# track-hold-lvc-sampler.net
KiCad netlist of a schematic drawn in EAGLE
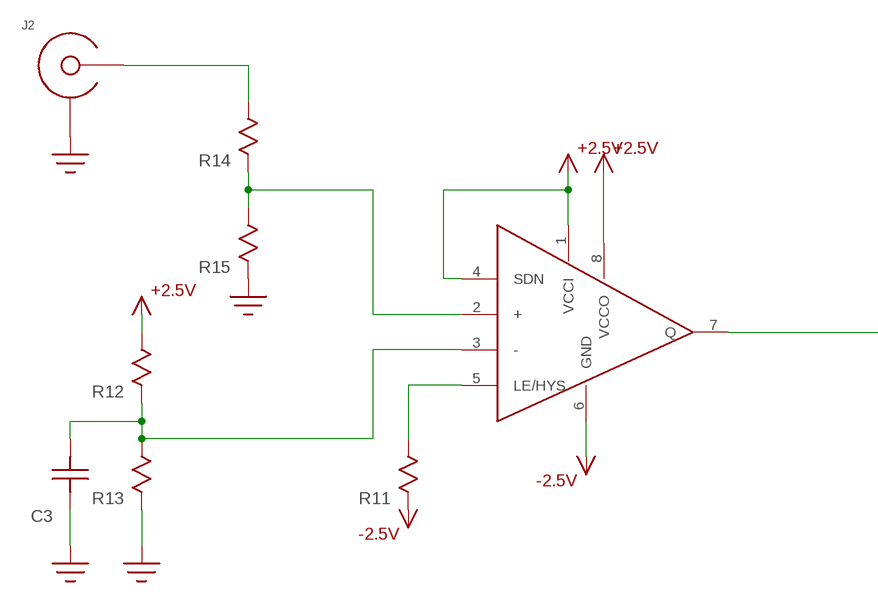
[diagram p0: schematic, sheet 1, part 1 of 2]
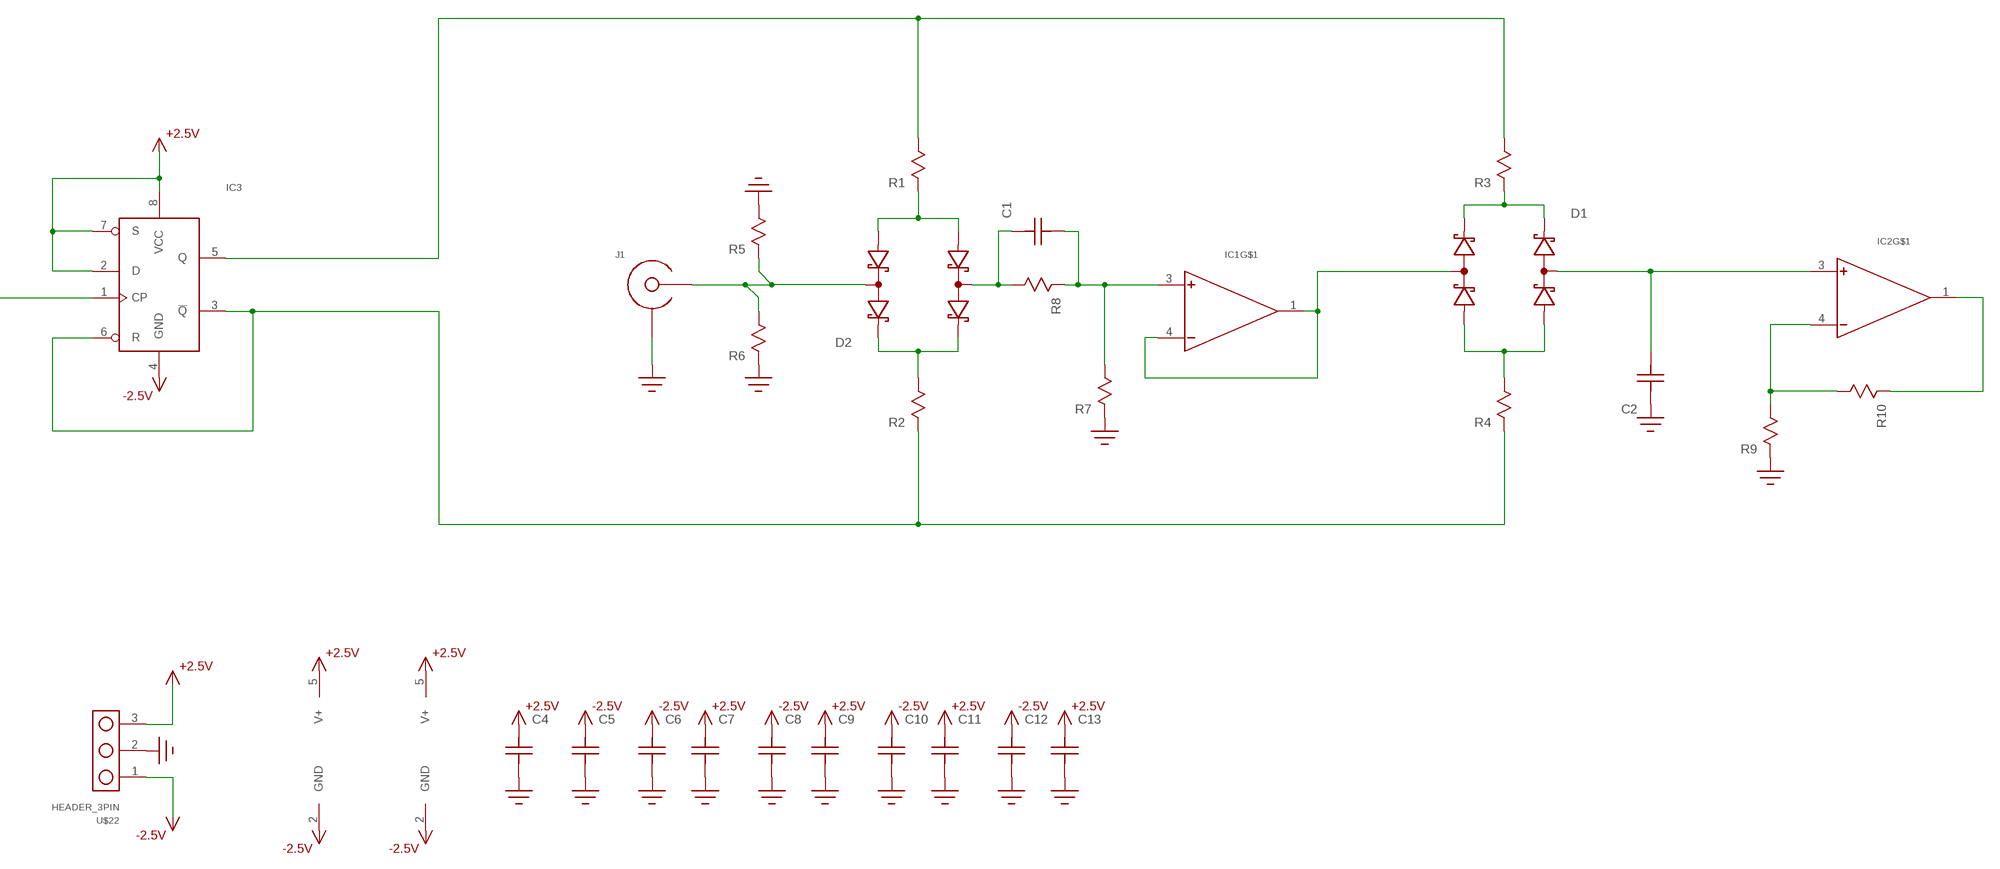
[diagram p1: schematic, sheet 1, part 2 of 2]

(export (version "E")
  (design (tool "Eeschema 10.0.6"))
  (components
    (comp (ref "C1")
      (value "C0603")
      (footprint "eagle-import:C0603")
      (libsource (lib "eagle-import") (part "C0603"))
    )
    (comp (ref "C2")
      (value "C0603")
      (footprint "eagle-import:C0603")
      (libsource (lib "eagle-import") (part "C0603"))
    )
    (comp (ref "C3")
      (value "C0603")
      (footprint "eagle-import:C0603")
      (libsource (lib "eagle-import") (part "C0603"))
    )
    (comp (ref "C4")
      (value "C1206")
      (footprint "eagle-import:1206")
      (libsource (lib "eagle-import") (part "C1206"))
    )
    (comp (ref "C5")
      (value "C1206")
      (footprint "eagle-import:1206")
      (libsource (lib "eagle-import") (part "C1206"))
    )
    (comp (ref "C6")
      (value "C0603")
      (footprint "eagle-import:C0603")
      (libsource (lib "eagle-import") (part "C0603"))
    )
    (comp (ref "C7")
      (value "C0603")
      (footprint "eagle-import:C0603")
      (libsource (lib "eagle-import") (part "C0603"))
    )
    (comp (ref "C8")
      (value "C0603")
      (footprint "eagle-import:C0603")
      (libsource (lib "eagle-import") (part "C0603"))
    )
    (comp (ref "C9")
      (value "C0603")
      (footprint "eagle-import:C0603")
      (libsource (lib "eagle-import") (part "C0603"))
    )
    (comp (ref "C10")
      (value "C0603")
      (footprint "eagle-import:C0603")
      (libsource (lib "eagle-import") (part "C0603"))
    )
    (comp (ref "C11")
      (value "C0603")
      (footprint "eagle-import:C0603")
      (libsource (lib "eagle-import") (part "C0603"))
    )
    (comp (ref "C12")
      (value "C0603")
      (footprint "eagle-import:C0603")
      (libsource (lib "eagle-import") (part "C0603"))
    )
    (comp (ref "C13")
      (value "C0603")
      (footprint "eagle-import:C0603")
      (libsource (lib "eagle-import") (part "C0603"))
    )
    (comp (ref "D1")
      (value "SMS3923-081")
      (footprint "eagle-import:SC-88")
      (libsource (lib "eagle-import") (part "SMS3923-081"))
    )
    (comp (ref "D2")
      (value "SMS3923-081")
      (footprint "eagle-import:SC-88")
      (libsource (lib "eagle-import") (part "SMS3923-081"))
    )
    (comp (ref "IC1")
      (value "ADA4000TSOT")
      (footprint "eagle-import:TSOT-23")
      (libsource (lib "eagle-import") (part "ADA4000TSOT"))
    )
    (comp (ref "IC2")
      (value "ADA4000TSOT")
      (footprint "eagle-import:TSOT-23")
      (libsource (lib "eagle-import") (part "ADA4000TSOT"))
    )
    (comp (ref "IC3")
      (value "74LVC2G74")
      (footprint "eagle-import:SSOP8")
      (libsource (lib "eagle-import") (part "74LVC2G74"))
    )
    (comp (ref "IC4")
      (value "ADCMP602")
      (footprint "eagle-import:MSOP8")
      (libsource (lib "eagle-import") (part "ADCMP602"))
    )
    (comp (ref "J1")
      (value "SMA-EDGE-LAUNCH4L-4020-TAPER-FIXED")
      (footprint "eagle-import:SMA_EDGE_LAUNCH_4L_4020_TAPER_FIXED")
      (libsource (lib "eagle-import") (part "SMA-EDGE-LAUNCH4L-4020-TAPER-FIXED"))
    )
    (comp (ref "J2")
      (value "SMA-EDGE-LAUNCH4L-4020-TAPER-FIXED")
      (footprint "eagle-import:SMA_EDGE_LAUNCH_4L_4020_TAPER_FIXED")
      (libsource (lib "eagle-import") (part "SMA-EDGE-LAUNCH4L-4020-TAPER-FIXED"))
    )
    (comp (ref "R1")
      (value "R0603")
      (footprint "eagle-import:R0603")
      (libsource (lib "eagle-import") (part "R0603"))
    )
    (comp (ref "R2")
      (value "R0603")
      (footprint "eagle-import:R0603")
      (libsource (lib "eagle-import") (part "R0603"))
    )
    (comp (ref "R3")
      (value "R0603")
      (footprint "eagle-import:R0603")
      (libsource (lib "eagle-import") (part "R0603"))
    )
    (comp (ref "R4")
      (value "R0603")
      (footprint "eagle-import:R0603")
      (libsource (lib "eagle-import") (part "R0603"))
    )
    (comp (ref "R5")
      (value "R0402")
      (footprint "eagle-import:0402")
      (libsource (lib "eagle-import") (part "R0402"))
    )
    (comp (ref "R6")
      (value "R0402")
      (footprint "eagle-import:0402")
      (libsource (lib "eagle-import") (part "R0402"))
    )
    (comp (ref "R7")
      (value "R0603")
      (footprint "eagle-import:R0603")
      (libsource (lib "eagle-import") (part "R0603"))
    )
    (comp (ref "R8")
      (value "R0603")
      (footprint "eagle-import:R0603")
      (libsource (lib "eagle-import") (part "R0603"))
    )
    (comp (ref "R9")
      (value "R0603")
      (footprint "eagle-import:R0603")
      (libsource (lib "eagle-import") (part "R0603"))
    )
    (comp (ref "R10")
      (value "R0603")
      (footprint "eagle-import:R0603")
      (libsource (lib "eagle-import") (part "R0603"))
    )
    (comp (ref "R11")
      (value "R0603")
      (footprint "eagle-import:R0603")
      (libsource (lib "eagle-import") (part "R0603"))
    )
    (comp (ref "R12")
      (value "R0603")
      (footprint "eagle-import:R0603")
      (libsource (lib "eagle-import") (part "R0603"))
    )
    (comp (ref "R13")
      (value "R0603")
      (footprint "eagle-import:R0603")
      (libsource (lib "eagle-import") (part "R0603"))
    )
    (comp (ref "R14")
      (value "R0603")
      (footprint "eagle-import:R0603")
      (libsource (lib "eagle-import") (part "R0603"))
    )
    (comp (ref "R15")
      (value "R0603")
      (footprint "eagle-import:R0603")
      (libsource (lib "eagle-import") (part "R0603"))
    )
    (comp (ref "U$22")
      (value "HEADER_3PIN")
      (footprint "eagle-import:HEADER_3PIN")
      (libsource (lib "eagle-import") (part "HEADER_3PIN"))
    )
  )
  (nets
    (net (code "1") (name "+2.5V") (class "Default")
      (node (ref "C11") (pin "P$2") (pinfunction "P$2_P$2") (pintype "bidirectional"))
      (node (ref "C13") (pin "P$2") (pinfunction "P$2_P$2") (pintype "bidirectional"))
      (node (ref "C4") (pin "P$2") (pinfunction "P$2_P$2") (pintype "bidirectional"))
      (node (ref "C7") (pin "P$2") (pinfunction "P$2_P$2") (pintype "bidirectional"))
      (node (ref "C9") (pin "P$2") (pinfunction "P$2_P$2") (pintype "bidirectional"))
      (node (ref "IC1") (pin "5") (pinfunction "V+_5") (pintype "bidirectional"))
      (node (ref "IC2") (pin "5") (pinfunction "V+_5") (pintype "bidirectional"))
      (node (ref "IC3") (pin "2") (pinfunction "D_2") (pintype "bidirectional"))
      (node (ref "IC3") (pin "7") (pinfunction "S_7") (pintype "bidirectional"))
      (node (ref "IC3") (pin "8") (pinfunction "VCC_8") (pintype "bidirectional"))
      (node (ref "IC4") (pin "1") (pinfunction "VCCI_1") (pintype "bidirectional"))
      (node (ref "IC4") (pin "4") (pinfunction "SDN_4") (pintype "bidirectional"))
      (node (ref "IC4") (pin "8") (pinfunction "VCCO_8") (pintype "bidirectional"))
      (node (ref "R12") (pin "P$2") (pinfunction "P$4_P$2") (pintype "bidirectional"))
      (node (ref "U$22") (pin "3") (pinfunction "3_3") (pintype "bidirectional"))
    )
    (net (code "2") (name "-2.5V") (class "Default")
      (node (ref "C10") (pin "P$2") (pinfunction "P$2_P$2") (pintype "bidirectional"))
      (node (ref "C12") (pin "P$2") (pinfunction "P$2_P$2") (pintype "bidirectional"))
      (node (ref "C5") (pin "P$2") (pinfunction "P$2_P$2") (pintype "bidirectional"))
      (node (ref "C6") (pin "P$2") (pinfunction "P$2_P$2") (pintype "bidirectional"))
      (node (ref "C8") (pin "P$2") (pinfunction "P$2_P$2") (pintype "bidirectional"))
      (node (ref "IC1") (pin "2") (pinfunction "GND_2") (pintype "bidirectional"))
      (node (ref "IC2") (pin "2") (pinfunction "GND_2") (pintype "bidirectional"))
      (node (ref "IC3") (pin "4") (pinfunction "GND_4") (pintype "bidirectional"))
      (node (ref "IC4") (pin "6") (pinfunction "GND_6") (pintype "bidirectional"))
      (node (ref "R11") (pin "P$1") (pinfunction "P$3_P$1") (pintype "bidirectional"))
      (node (ref "U$22") (pin "1") (pinfunction "1_1") (pintype "bidirectional"))
    )
    (net (code "3") (name "GND") (class "Default")
      (node (ref "C10") (pin "P$1") (pinfunction "P$1_P$1") (pintype "bidirectional"))
      (node (ref "C11") (pin "P$1") (pinfunction "P$1_P$1") (pintype "bidirectional"))
      (node (ref "C12") (pin "P$1") (pinfunction "P$1_P$1") (pintype "bidirectional"))
      (node (ref "C13") (pin "P$1") (pinfunction "P$1_P$1") (pintype "bidirectional"))
      (node (ref "C2") (pin "P$2") (pinfunction "P$2_P$2") (pintype "bidirectional"))
      (node (ref "C3") (pin "P$2") (pinfunction "P$2_P$2") (pintype "bidirectional"))
      (node (ref "C4") (pin "P$1") (pinfunction "P$1_P$1") (pintype "bidirectional"))
      (node (ref "C5") (pin "P$1") (pinfunction "P$1_P$1") (pintype "bidirectional"))
      (node (ref "C6") (pin "P$1") (pinfunction "P$1_P$1") (pintype "bidirectional"))
      (node (ref "C7") (pin "P$1") (pinfunction "P$1_P$1") (pintype "bidirectional"))
      (node (ref "C8") (pin "P$1") (pinfunction "P$1_P$1") (pintype "bidirectional"))
      (node (ref "C9") (pin "P$1") (pinfunction "P$1_P$1") (pintype "bidirectional"))
      (node (ref "J1") (pin "BOTTOM_GND") (pinfunction "SHIELD_BOTTOM_GND") (pintype "bidirectional"))
      (node (ref "J1") (pin "GND@1") (pinfunction "SHIELD_GND@1") (pintype "bidirectional"))
      (node (ref "J1") (pin "GND@14") (pinfunction "SHIELD_GND@14") (pintype "bidirectional"))
      (node (ref "J1") (pin "GND@15") (pinfunction "SHIELD_GND@15") (pintype "bidirectional"))
      (node (ref "J1") (pin "GND@16") (pinfunction "SHIELD_GND@16") (pintype "bidirectional"))
      (node (ref "J1") (pin "GND@17") (pinfunction "SHIELD_GND@17") (pintype "bidirectional"))
      (node (ref "J1") (pin "GND@2") (pinfunction "SHIELD_GND@2") (pintype "bidirectional"))
      (node (ref "J1") (pin "GND@3") (pinfunction "SHIELD_GND@3") (pintype "bidirectional"))
      (node (ref "J1") (pin "GND@4") (pinfunction "SHIELD_GND@4") (pintype "bidirectional"))
      (node (ref "J1") (pin "GND@5") (pinfunction "SHIELD_GND@5") (pintype "bidirectional"))
      (node (ref "J1") (pin "GND@6") (pinfunction "SHIELD_GND@6") (pintype "bidirectional"))
      (node (ref "J1") (pin "GND@7") (pinfunction "SHIELD_GND@7") (pintype "bidirectional"))
      (node (ref "J1") (pin "GND@8") (pinfunction "SHIELD_GND@8") (pintype "bidirectional"))
      (node (ref "J1") (pin "GND_PAD1") (pinfunction "SHIELD_GND_PAD1") (pintype "bidirectional"))
      (node (ref "J1") (pin "GND_PAD2") (pinfunction "SHIELD_GND_PAD2") (pintype "bidirectional"))
      (node (ref "J1") (pin "P$1") (pinfunction "SHIELD_P$1") (pintype "bidirectional"))
      (node (ref "J1") (pin "P$2") (pinfunction "SHIELD_P$2") (pintype "bidirectional"))
      (node (ref "J2") (pin "BOTTOM_GND") (pinfunction "SHIELD_BOTTOM_GND") (pintype "bidirectional"))
      (node (ref "J2") (pin "GND@1") (pinfunction "SHIELD_GND@1") (pintype "bidirectional"))
      (node (ref "J2") (pin "GND@14") (pinfunction "SHIELD_GND@14") (pintype "bidirectional"))
      (node (ref "J2") (pin "GND@15") (pinfunction "SHIELD_GND@15") (pintype "bidirectional"))
      (node (ref "J2") (pin "GND@16") (pinfunction "SHIELD_GND@16") (pintype "bidirectional"))
      (node (ref "J2") (pin "GND@17") (pinfunction "SHIELD_GND@17") (pintype "bidirectional"))
      (node (ref "J2") (pin "GND@2") (pinfunction "SHIELD_GND@2") (pintype "bidirectional"))
      (node (ref "J2") (pin "GND@3") (pinfunction "SHIELD_GND@3") (pintype "bidirectional"))
      (node (ref "J2") (pin "GND@4") (pinfunction "SHIELD_GND@4") (pintype "bidirectional"))
      (node (ref "J2") (pin "GND@5") (pinfunction "SHIELD_GND@5") (pintype "bidirectional"))
      (node (ref "J2") (pin "GND@6") (pinfunction "SHIELD_GND@6") (pintype "bidirectional"))
      (node (ref "J2") (pin "GND@7") (pinfunction "SHIELD_GND@7") (pintype "bidirectional"))
      (node (ref "J2") (pin "GND@8") (pinfunction "SHIELD_GND@8") (pintype "bidirectional"))
      (node (ref "J2") (pin "GND_PAD1") (pinfunction "SHIELD_GND_PAD1") (pintype "bidirectional"))
      (node (ref "J2") (pin "GND_PAD2") (pinfunction "SHIELD_GND_PAD2") (pintype "bidirectional"))
      (node (ref "J2") (pin "P$1") (pinfunction "SHIELD_P$1") (pintype "bidirectional"))
      (node (ref "J2") (pin "P$2") (pinfunction "SHIELD_P$2") (pintype "bidirectional"))
      (node (ref "R13") (pin "P$1") (pinfunction "P$3_P$1") (pintype "bidirectional"))
      (node (ref "R15") (pin "P$1") (pinfunction "P$3_P$1") (pintype "bidirectional"))
      (node (ref "R5") (pin "2") (pinfunction "P$4_2") (pintype "bidirectional"))
      (node (ref "R6") (pin "1") (pinfunction "P$3_1") (pintype "bidirectional"))
      (node (ref "R7") (pin "P$1") (pinfunction "P$3_P$1") (pintype "bidirectional"))
      (node (ref "R9") (pin "P$1") (pinfunction "P$3_P$1") (pintype "bidirectional"))
      (node (ref "U$22") (pin "2") (pinfunction "2_2") (pintype "bidirectional"))
    )
    (net (code "4") (name "Net-(D1-ANODE0)") (class "Default")
      (node (ref "D1") (pin "1") (pinfunction "ANODE0_1") (pintype "bidirectional"))
      (node (ref "D1") (pin "6") (pinfunction "ANODE1_6") (pintype "bidirectional"))
      (node (ref "R4") (pin "P$2") (pinfunction "P$4_P$2") (pintype "bidirectional"))
    )
    (net (code "5") (name "Net-(D1-CATHODE0)") (class "Default")
      (node (ref "D1") (pin "3") (pinfunction "CATHODE0_3") (pintype "bidirectional"))
      (node (ref "D1") (pin "4") (pinfunction "CATHODE1_4") (pintype "bidirectional"))
      (node (ref "R3") (pin "P$1") (pinfunction "P$3_P$1") (pintype "bidirectional"))
    )
    (net (code "6") (name "Net-(D1-COMMON0)") (class "Default")
      (node (ref "C2") (pin "P$1") (pinfunction "P$1_P$1") (pintype "bidirectional"))
      (node (ref "D1") (pin "2") (pinfunction "COMMON0_2") (pintype "bidirectional"))
      (node (ref "IC2") (pin "3") (pinfunction "+_3") (pintype "bidirectional"))
    )
    (net (code "7") (name "Net-(D1-COMMON1)") (class "Default")
      (node (ref "D1") (pin "5") (pinfunction "COMMON1_5") (pintype "bidirectional"))
      (node (ref "IC1") (pin "1") (pinfunction "OUT_1") (pintype "bidirectional"))
      (node (ref "IC1") (pin "4") (pinfunction "-_4") (pintype "bidirectional"))
    )
    (net (code "8") (name "Net-(D2-ANODE0)") (class "Default")
      (node (ref "D2") (pin "1") (pinfunction "ANODE0_1") (pintype "bidirectional"))
      (node (ref "D2") (pin "6") (pinfunction "ANODE1_6") (pintype "bidirectional"))
      (node (ref "R1") (pin "P$1") (pinfunction "P$3_P$1") (pintype "bidirectional"))
    )
    (net (code "9") (name "Net-(D2-CATHODE0)") (class "Default")
      (node (ref "D2") (pin "3") (pinfunction "CATHODE0_3") (pintype "bidirectional"))
      (node (ref "D2") (pin "4") (pinfunction "CATHODE1_4") (pintype "bidirectional"))
      (node (ref "R2") (pin "P$2") (pinfunction "P$4_P$2") (pintype "bidirectional"))
    )
    (net (code "10") (name "Net-(D2-COMMON0)") (class "Default")
      (node (ref "D2") (pin "2") (pinfunction "COMMON0_2") (pintype "bidirectional"))
      (node (ref "J1") (pin "CENTER@1") (pinfunction "CENTER_CENTER@1") (pintype "bidirectional"))
      (node (ref "J1") (pin "P$3") (pinfunction "CENTER_P$3") (pintype "bidirectional"))
      (node (ref "R5") (pin "1") (pinfunction "P$3_1") (pintype "bidirectional"))
      (node (ref "R6") (pin "2") (pinfunction "P$4_2") (pintype "bidirectional"))
    )
    (net (code "11") (name "Net-(D2-COMMON1)") (class "Default")
      (node (ref "C1") (pin "P$2") (pinfunction "P$2_P$2") (pintype "bidirectional"))
      (node (ref "D2") (pin "5") (pinfunction "COMMON1_5") (pintype "bidirectional"))
      (node (ref "R8") (pin "P$2") (pinfunction "P$4_P$2") (pintype "bidirectional"))
    )
    (net (code "12") (name "Net-(IC1A-+)") (class "Default")
      (node (ref "C1") (pin "P$1") (pinfunction "P$1_P$1") (pintype "bidirectional"))
      (node (ref "IC1") (pin "3") (pinfunction "+_3") (pintype "bidirectional"))
      (node (ref "R7") (pin "P$2") (pinfunction "P$4_P$2") (pintype "bidirectional"))
      (node (ref "R8") (pin "P$1") (pinfunction "P$3_P$1") (pintype "bidirectional"))
    )
    (net (code "13") (name "Net-(IC2A--)") (class "Default")
      (node (ref "IC2") (pin "4") (pinfunction "-_4") (pintype "bidirectional"))
      (node (ref "R10") (pin "P$2") (pinfunction "P$4_P$2") (pintype "bidirectional"))
      (node (ref "R9") (pin "P$2") (pinfunction "P$4_P$2") (pintype "bidirectional"))
    )
    (net (code "14") (name "Net-(IC2A-OUT)") (class "Default")
      (node (ref "IC2") (pin "1") (pinfunction "OUT_1") (pintype "bidirectional"))
      (node (ref "R10") (pin "P$1") (pinfunction "P$3_P$1") (pintype "bidirectional"))
    )
    (net (code "15") (name "Net-(IC3-CP)") (class "Default")
      (node (ref "IC3") (pin "1") (pinfunction "CP_1") (pintype "bidirectional"))
      (node (ref "IC4") (pin "7") (pinfunction "Q_7") (pintype "bidirectional"))
    )
    (net (code "16") (name "Net-(IC3-Q)") (class "Default")
      (node (ref "IC3") (pin "5") (pinfunction "Q_5") (pintype "bidirectional"))
      (node (ref "R1") (pin "P$2") (pinfunction "P$4_P$2") (pintype "bidirectional"))
      (node (ref "R3") (pin "P$2") (pinfunction "P$4_P$2") (pintype "bidirectional"))
    )
    (net (code "17") (name "Net-(IC3-R)") (class "Default")
      (node (ref "IC3") (pin "3") (pinfunction "~{Q}_3") (pintype "bidirectional"))
      (node (ref "IC3") (pin "6") (pinfunction "R_6") (pintype "bidirectional"))
      (node (ref "R2") (pin "P$1") (pinfunction "P$3_P$1") (pintype "bidirectional"))
      (node (ref "R4") (pin "P$1") (pinfunction "P$3_P$1") (pintype "bidirectional"))
    )
    (net (code "18") (name "Net-(IC4-+)") (class "Default")
      (node (ref "IC4") (pin "2") (pinfunction "+_2") (pintype "bidirectional"))
      (node (ref "R14") (pin "P$1") (pinfunction "P$3_P$1") (pintype "bidirectional"))
      (node (ref "R15") (pin "P$2") (pinfunction "P$4_P$2") (pintype "bidirectional"))
    )
    (net (code "19") (name "Net-(IC4--)") (class "Default")
      (node (ref "C3") (pin "P$1") (pinfunction "P$1_P$1") (pintype "bidirectional"))
      (node (ref "IC4") (pin "3") (pinfunction "-_3") (pintype "bidirectional"))
      (node (ref "R12") (pin "P$1") (pinfunction "P$3_P$1") (pintype "bidirectional"))
      (node (ref "R13") (pin "P$2") (pinfunction "P$4_P$2") (pintype "bidirectional"))
    )
    (net (code "20") (name "Net-(IC4-LE{slash}HYS)") (class "Default")
      (node (ref "IC4") (pin "5") (pinfunction "LE/HYS_5") (pintype "bidirectional"))
      (node (ref "R11") (pin "P$2") (pinfunction "P$4_P$2") (pintype "bidirectional"))
    )
    (net (code "21") (name "Net-(R14-P$4)") (class "Default")
      (node (ref "J2") (pin "CENTER@1") (pinfunction "CENTER_CENTER@1") (pintype "bidirectional"))
      (node (ref "J2") (pin "P$3") (pinfunction "CENTER_P$3") (pintype "bidirectional"))
      (node (ref "R14") (pin "P$2") (pinfunction "P$4_P$2") (pintype "bidirectional"))
    )
  )
)
